# LT3015_LT1963_TPS74401.net
KiCad netlist of a schematic drawn in Altium Designer
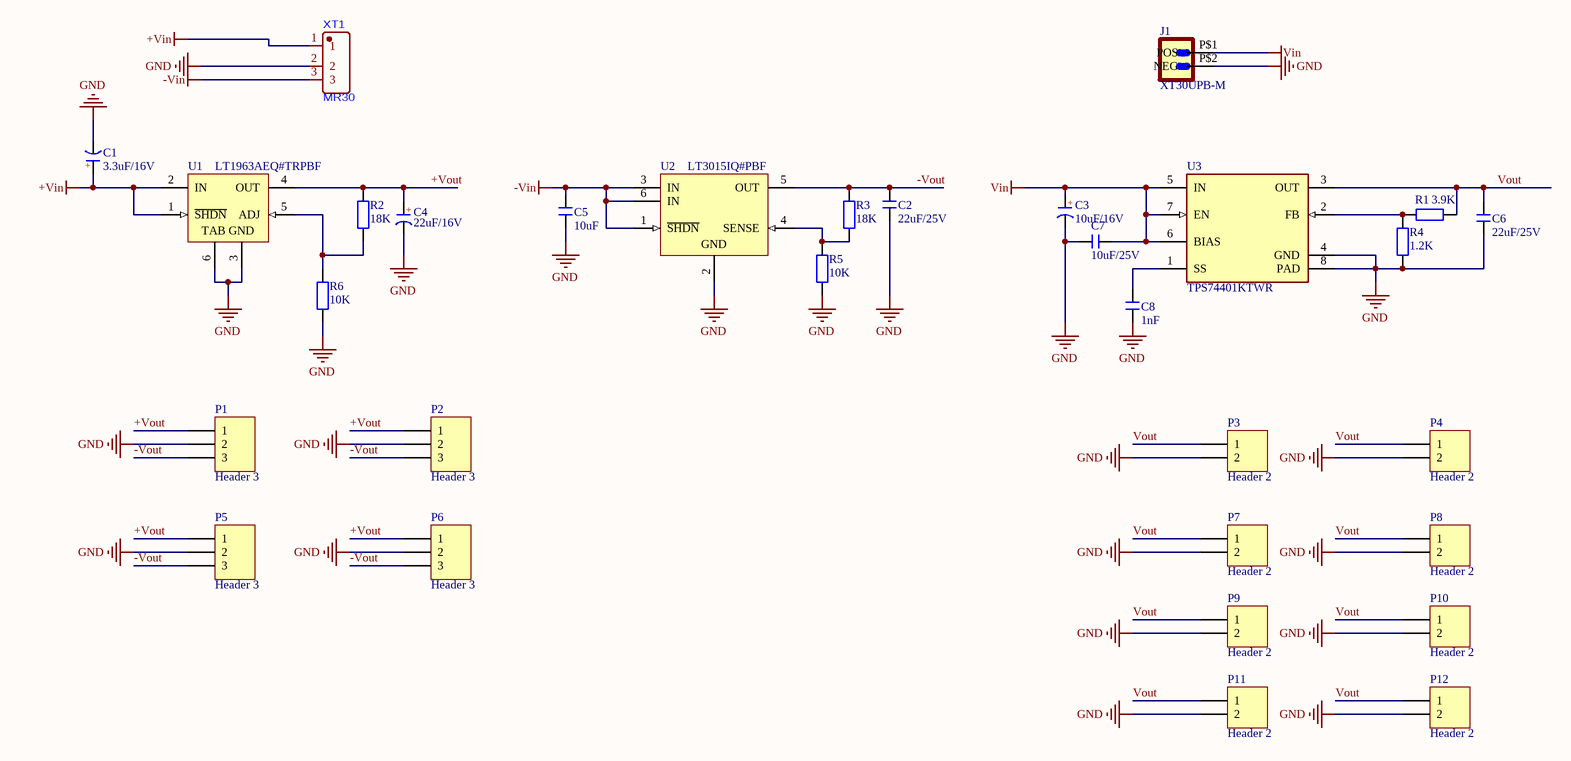
[diagram p0: LT3015_LT1963_TPS74401.SchDoc]

(export (version "E")
  (design (tool "Eeschema 10.0.6"))
  (components
    (comp (ref "C1")
      (value "3.3uF/16V")
      (footprint "CD A(3216)")
      (description "贴片钽电容")
      (libsource (lib "01 - 电容-电阻-电感") (part "CT"))
    )
    (comp (ref "C2")
      (value "22uF/25V")
      (footprint "C 0805_L")
      (description "贴片电容")
      (libsource (lib "01 - 电容-电阻-电感") (part "C"))
    )
    (comp (ref "C3")
      (value "10uF/16V")
      (footprint "CD A(3216)")
      (description "贴片钽电容")
      (libsource (lib "01 - 电容-电阻-电感") (part "CT"))
    )
    (comp (ref "C4")
      (value "22uF/16V")
      (footprint "CD A(3216)")
      (description "贴片钽电容")
      (libsource (lib "01 - 电容-电阻-电感") (part "CT"))
    )
    (comp (ref "C5")
      (value "10uF")
      (footprint "C 0805_L")
      (description "贴片电容")
      (libsource (lib "01 - 电容-电阻-电感") (part "C"))
    )
    (comp (ref "C6")
      (value "22uF/25V")
      (footprint "C 0805_L")
      (description "贴片电容")
      (libsource (lib "01 - 电容-电阻-电感") (part "C"))
    )
    (comp (ref "C7")
      (value "10uF/25V")
      (footprint "C 0805_L")
      (description "贴片电容")
      (libsource (lib "01 - 电容-电阻-电感") (part "C"))
    )
    (comp (ref "C8")
      (value "1nF")
      (footprint "C 0603_L")
      (description "贴片电容")
      (libsource (lib "01 - 电容-电阻-电感") (part "C"))
    )
    (comp (ref "J1")
      (value "XT30UPB-M")
      (footprint "XT30UPB-M")
      (description "Socket; DC supply; XT30; male; PIN: 2; on PCBs; THT; yellow; 15A; 500V")
      (fields (field (name "MF") "amass"))
      (libsource (lib "XT30U") (part "XT30UPB-M"))
    )
    (comp (ref "P1")
      (value "Header 3")
      (footprint "HDR1X3")
      (description "Header, 3-Pin")
      (fields (field (name "PUBLISHER") "Altium Limited"))
      (libsource (lib "Miscellaneous Connectors") (part "Header 3"))
    )
    (comp (ref "P2")
      (value "Header 3")
      (footprint "HDR1X3")
      (description "Header, 3-Pin")
      (fields (field (name "PUBLISHER") "Altium Limited"))
      (libsource (lib "Miscellaneous Connectors") (part "Header 3"))
    )
    (comp (ref "P3")
      (value "Header 2")
      (footprint "HDR1X2")
      (description "Header, 2-Pin")
      (fields (field (name "PUBLISHER") "Altium Limited"))
      (libsource (lib "Miscellaneous Connectors") (part "Header 2"))
    )
    (comp (ref "P4")
      (value "Header 2")
      (footprint "HDR1X2")
      (description "Header, 2-Pin")
      (fields (field (name "PUBLISHER") "Altium Limited"))
      (libsource (lib "Miscellaneous Connectors") (part "Header 2"))
    )
    (comp (ref "P5")
      (value "Header 3")
      (footprint "HDR1X3")
      (description "Header, 3-Pin")
      (fields (field (name "PUBLISHER") "Altium Limited"))
      (libsource (lib "Miscellaneous Connectors") (part "Header 3"))
    )
    (comp (ref "P6")
      (value "Header 3")
      (footprint "HDR1X3")
      (description "Header, 3-Pin")
      (fields (field (name "PUBLISHER") "Altium Limited"))
      (libsource (lib "Miscellaneous Connectors") (part "Header 3"))
    )
    (comp (ref "P7")
      (value "Header 2")
      (footprint "HDR1X2")
      (description "Header, 2-Pin")
      (fields (field (name "PUBLISHER") "Altium Limited"))
      (libsource (lib "Miscellaneous Connectors") (part "Header 2"))
    )
    (comp (ref "P8")
      (value "Header 2")
      (footprint "HDR1X2")
      (description "Header, 2-Pin")
      (fields (field (name "PUBLISHER") "Altium Limited"))
      (libsource (lib "Miscellaneous Connectors") (part "Header 2"))
    )
    (comp (ref "P9")
      (value "Header 2")
      (footprint "HDR1X2")
      (description "Header, 2-Pin")
      (fields (field (name "PUBLISHER") "Altium Limited"))
      (libsource (lib "Miscellaneous Connectors") (part "Header 2"))
    )
    (comp (ref "P10")
      (value "Header 2")
      (footprint "HDR1X2")
      (description "Header, 2-Pin")
      (fields (field (name "PUBLISHER") "Altium Limited"))
      (libsource (lib "Miscellaneous Connectors") (part "Header 2"))
    )
    (comp (ref "P11")
      (value "Header 2")
      (footprint "HDR1X2")
      (description "Header, 2-Pin")
      (fields (field (name "PUBLISHER") "Altium Limited"))
      (libsource (lib "Miscellaneous Connectors") (part "Header 2"))
    )
    (comp (ref "P12")
      (value "Header 2")
      (footprint "HDR1X2")
      (description "Header, 2-Pin")
      (fields (field (name "PUBLISHER") "Altium Limited"))
      (libsource (lib "Miscellaneous Connectors") (part "Header 2"))
    )
    (comp (ref "R1")
      (value "3.9K")
      (footprint "R 0603_L")
      (description "贴片电阻")
      (libsource (lib "01 - 电容-电阻-电感") (part "R"))
    )
    (comp (ref "R2")
      (value "18K")
      (footprint "R 0603_L")
      (description "贴片电阻")
      (libsource (lib "01 - 电容-电阻-电感") (part "R"))
    )
    (comp (ref "R3")
      (value "18K")
      (footprint "R 0603_L")
      (description "贴片电阻")
      (libsource (lib "01 - 电容-电阻-电感") (part "R"))
    )
    (comp (ref "R4")
      (value "1.2K")
      (footprint "R 0603_L")
      (description "贴片电阻")
      (libsource (lib "01 - 电容-电阻-电感") (part "R"))
    )
    (comp (ref "R5")
      (value "10K")
      (footprint "R 0603_L")
      (description "贴片电阻")
      (libsource (lib "01 - 电容-电阻-电感") (part "R"))
    )
    (comp (ref "R6")
      (value "10K")
      (footprint "R 0603_L")
      (description "贴片电阻")
      (libsource (lib "01 - 电容-电阻-电感") (part "R"))
    )
    (comp (ref "U1")
      (value "LT1963AEQ#TRPBF")
      (footprint "LT-Q-5_L")
      (fields (field (name "MANUFACTURER") "Linear Technology"))
      (libsource (lib "Altium Content Vault") (part "LT-LT1764A_1963A_1965-Q-5"))
    )
    (comp (ref "U2")
      (value "LT3015IQ#PBF")
      (footprint "LT-Q-5_L")
      (fields (field (name "MANUFACTURER") "Linear Technology"))
      (libsource (lib "Altium Content Vault") (part "LT-LT3015-Q-5"))
    )
    (comp (ref "U3")
      (value "TPS74401KTWR")
      (footprint "FP-KTW0007A-MFG")
      (description "IC REG LIN POS ADJ 3A DDPAK")
      (libsource (lib "Altium Content Vault") (part "bd6f198d1d5ffa115f1ab79ffe109b0"))
    )
    (comp (ref "XT1") (value "MR30") (footprint "CONN-TH_MR30-M") (libsource (lib "MR30") (part "MR30")))
  )
  (nets
    (net (code "1") (name "+Vin") (class "Default")
      (node (ref "C1") (pin "1") (pinfunction "A_1") (pintype "passive"))
      (node (ref "U1") (pin "1") (pinfunction "~{SHDN}_1") (pintype "input"))
      (node (ref "U1") (pin "2") (pinfunction "IN_2") (pintype "power_in"))
      (node (ref "XT1") (pin "1") (pinfunction "1_1") (pintype "passive"))
    )
    (net (code "2") (name "-Vin") (class "Default")
      (node (ref "C5") (pin "2") (pinfunction "2_2") (pintype "passive"))
      (node (ref "U2") (pin "1") (pinfunction "~{SHDN}_1") (pintype "input"))
      (node (ref "U2") (pin "3") (pinfunction "IN_3") (pintype "power_in"))
      (node (ref "U2") (pin "6") (pinfunction "IN_6") (pintype "power_in"))
      (node (ref "XT1") (pin "3") (pinfunction "3_3") (pintype "passive"))
    )
    (net (code "3") (name "/+Vout") (class "Default")
      (node (ref "C4") (pin "1") (pinfunction "A_1") (pintype "passive"))
      (node (ref "P1") (pin "1") (pinfunction "1_1") (pintype "passive"))
      (node (ref "P2") (pin "1") (pinfunction "1_1") (pintype "passive"))
      (node (ref "P5") (pin "1") (pinfunction "1_1") (pintype "passive"))
      (node (ref "P6") (pin "1") (pinfunction "1_1") (pintype "passive"))
      (node (ref "R2") (pin "2") (pinfunction "2_2") (pintype "passive"))
      (node (ref "U1") (pin "4") (pinfunction "OUT_4") (pintype "power_in"))
    )
    (net (code "4") (name "/-Vout") (class "Default")
      (node (ref "C2") (pin "2") (pinfunction "2_2") (pintype "passive"))
      (node (ref "P1") (pin "3") (pinfunction "3_3") (pintype "passive"))
      (node (ref "P2") (pin "3") (pinfunction "3_3") (pintype "passive"))
      (node (ref "P5") (pin "3") (pinfunction "3_3") (pintype "passive"))
      (node (ref "P6") (pin "3") (pinfunction "3_3") (pintype "passive"))
      (node (ref "R3") (pin "2") (pinfunction "2_2") (pintype "passive"))
      (node (ref "U2") (pin "5") (pinfunction "OUT_5") (pintype "power_in"))
    )
    (net (code "5") (name "/Vout") (class "Default")
      (node (ref "C6") (pin "2") (pinfunction "2_2") (pintype "passive"))
      (node (ref "P10") (pin "1") (pinfunction "1_1") (pintype "passive"))
      (node (ref "P11") (pin "1") (pinfunction "1_1") (pintype "passive"))
      (node (ref "P12") (pin "1") (pinfunction "1_1") (pintype "passive"))
      (node (ref "P3") (pin "1") (pinfunction "1_1") (pintype "passive"))
      (node (ref "P4") (pin "1") (pinfunction "1_1") (pintype "passive"))
      (node (ref "P7") (pin "1") (pinfunction "1_1") (pintype "passive"))
      (node (ref "P8") (pin "1") (pinfunction "1_1") (pintype "passive"))
      (node (ref "P9") (pin "1") (pinfunction "1_1") (pintype "passive"))
      (node (ref "R1") (pin "1") (pinfunction "1_1") (pintype "passive"))
      (node (ref "U3") (pin "3") (pinfunction "OUT_3") (pintype "power_in"))
    )
    (net (code "6") (name "GND") (class "Default")
      (node (ref "C1") (pin "2") (pinfunction "K_2") (pintype "passive"))
      (node (ref "C2") (pin "1") (pinfunction "1_1") (pintype "passive"))
      (node (ref "C3") (pin "2") (pinfunction "K_2") (pintype "passive"))
      (node (ref "C4") (pin "2") (pinfunction "K_2") (pintype "passive"))
      (node (ref "C5") (pin "1") (pinfunction "1_1") (pintype "passive"))
      (node (ref "C6") (pin "1") (pinfunction "1_1") (pintype "passive"))
      (node (ref "C7") (pin "2") (pinfunction "2_2") (pintype "passive"))
      (node (ref "C8") (pin "1") (pinfunction "1_1") (pintype "passive"))
      (node (ref "J1") (pin "P$2") (pinfunction "NEG_P$2") (pintype "passive"))
      (node (ref "P1") (pin "2") (pinfunction "2_2") (pintype "passive"))
      (node (ref "P10") (pin "2") (pinfunction "2_2") (pintype "passive"))
      (node (ref "P11") (pin "2") (pinfunction "2_2") (pintype "passive"))
      (node (ref "P12") (pin "2") (pinfunction "2_2") (pintype "passive"))
      (node (ref "P2") (pin "2") (pinfunction "2_2") (pintype "passive"))
      (node (ref "P3") (pin "2") (pinfunction "2_2") (pintype "passive"))
      (node (ref "P4") (pin "2") (pinfunction "2_2") (pintype "passive"))
      (node (ref "P5") (pin "2") (pinfunction "2_2") (pintype "passive"))
      (node (ref "P6") (pin "2") (pinfunction "2_2") (pintype "passive"))
      (node (ref "P7") (pin "2") (pinfunction "2_2") (pintype "passive"))
      (node (ref "P8") (pin "2") (pinfunction "2_2") (pintype "passive"))
      (node (ref "P9") (pin "2") (pinfunction "2_2") (pintype "passive"))
      (node (ref "R4") (pin "1") (pinfunction "1_1") (pintype "passive"))
      (node (ref "R5") (pin "1") (pinfunction "1_1") (pintype "passive"))
      (node (ref "R6") (pin "1") (pinfunction "1_1") (pintype "passive"))
      (node (ref "U1") (pin "3") (pinfunction "GND_3") (pintype "power_in"))
      (node (ref "U1") (pin "6") (pinfunction "TAB_6") (pintype "power_in"))
      (node (ref "U2") (pin "2") (pinfunction "GND_2") (pintype "power_in"))
      (node (ref "U3") (pin "4") (pinfunction "GND_4") (pintype "power_in"))
      (node (ref "U3") (pin "8") (pinfunction "PAD_8") (pintype "power_in"))
      (node (ref "XT1") (pin "2") (pinfunction "2_2") (pintype "passive"))
    )
    (net (code "7") (name "Net-(U1-ADJ)") (class "Default")
      (node (ref "R2") (pin "1") (pinfunction "1_1") (pintype "passive"))
      (node (ref "R6") (pin "2") (pinfunction "2_2") (pintype "passive"))
      (node (ref "U1") (pin "5") (pinfunction "ADJ_5") (pintype "input"))
    )
    (net (code "8") (name "Net-(U2-SENSE)") (class "Default")
      (node (ref "R3") (pin "1") (pinfunction "1_1") (pintype "passive"))
      (node (ref "R5") (pin "2") (pinfunction "2_2") (pintype "passive"))
      (node (ref "U2") (pin "4") (pinfunction "SENSE_4") (pintype "input"))
    )
    (net (code "9") (name "Net-(U3-FB)") (class "Default")
      (node (ref "R1") (pin "2") (pinfunction "2_2") (pintype "passive"))
      (node (ref "R4") (pin "2") (pinfunction "2_2") (pintype "passive"))
      (node (ref "U3") (pin "2") (pinfunction "FB_2") (pintype "input"))
    )
    (net (code "10") (name "Net-(U3-SS)") (class "Default")
      (node (ref "C8") (pin "2") (pinfunction "2_2") (pintype "passive"))
      (node (ref "U3") (pin "1") (pinfunction "SS_1") (pintype "passive"))
    )
    (net (code "11") (name "Vin") (class "Default")
      (node (ref "C3") (pin "1") (pinfunction "A_1") (pintype "passive"))
      (node (ref "C7") (pin "1") (pinfunction "1_1") (pintype "passive"))
      (node (ref "J1") (pin "P$1") (pinfunction "POS_P$1") (pintype "passive"))
      (node (ref "U3") (pin "5") (pinfunction "IN_5") (pintype "power_in"))
      (node (ref "U3") (pin "6") (pinfunction "BIAS_6") (pintype "power_in"))
      (node (ref "U3") (pin "7") (pinfunction "EN_7") (pintype "input"))
    )
  )
)
